# ACCUMULATOR.net
KiCad netlist of a schematic drawn in EAGLE
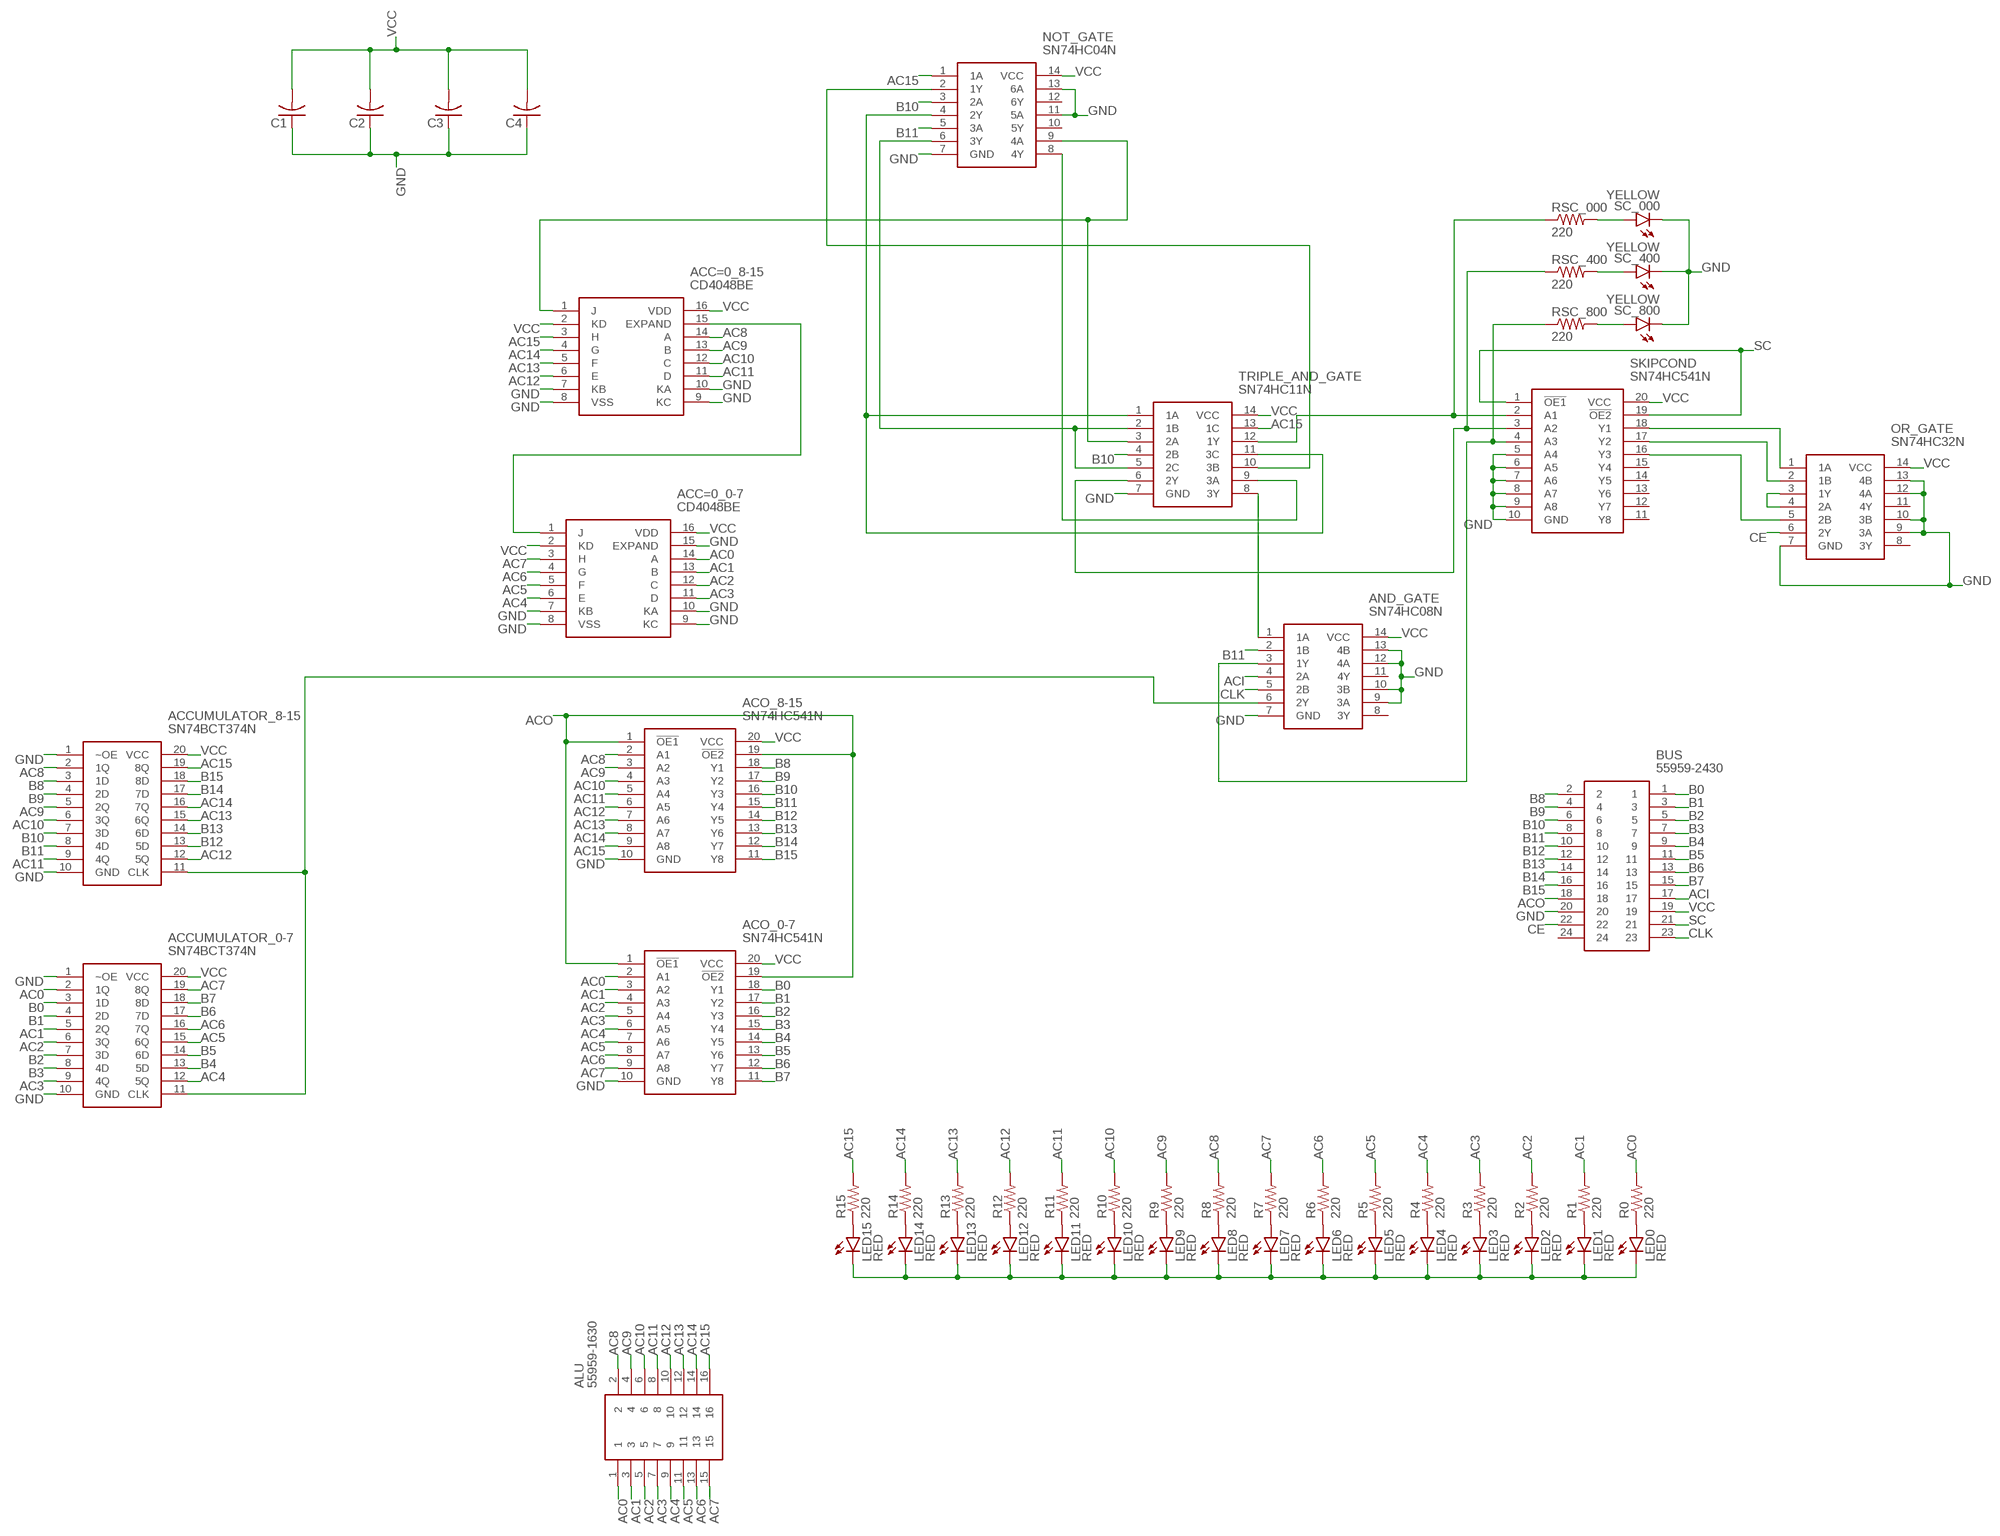
[diagram p0: schematic, sheet 1]

(export (version "E")
  (design (tool "Eeschema 10.0.6"))
  (components
    (comp (ref "ACC=0_0-7")
      (value "CD4048BE")
      (footprint "eagle-import:DIP254P762X508-16")
      (fields (field (name "MOUSER_PART_NUMBER") "595-CD4048BE"))
      (libsource (lib "eagle-import") (part "CD4048BE"))
    )
    (comp (ref "ACC=0_8-15")
      (value "CD4048BE")
      (footprint "eagle-import:DIP254P762X508-16")
      (fields (field (name "MOUSER_PART_NUMBER") "595-CD4048BE"))
      (libsource (lib "eagle-import") (part "CD4048BE"))
    )
    (comp (ref "ACCUMULATOR_0-7")
      (value "SN74BCT374N")
      (footprint "eagle-import:DIP254P762X508-20")
      (fields (field (name "MOUSER_PART_NUMBER") "595-SN74BCT374N"))
      (libsource (lib "eagle-import") (part "SN74BCT374N"))
    )
    (comp (ref "ACCUMULATOR_8-15")
      (value "SN74BCT374N")
      (footprint "eagle-import:DIP254P762X508-20")
      (fields (field (name "MOUSER_PART_NUMBER") "595-SN74BCT374N"))
      (libsource (lib "eagle-import") (part "SN74BCT374N"))
    )
    (comp (ref "ACO_0-7")
      (value "SN74HC541N")
      (footprint "eagle-import:DIP794W53P254L2540H508Q20N")
      (fields (field (name "MOUSER_PART_NUMBER") "595-SN74HC541N"))
      (libsource (lib "eagle-import") (part "SN74HC541N"))
    )
    (comp (ref "ACO_8-15")
      (value "SN74HC541N")
      (footprint "eagle-import:DIP794W53P254L2540H508Q20N")
      (fields (field (name "MOUSER_PART_NUMBER") "595-SN74HC541N"))
      (libsource (lib "eagle-import") (part "SN74HC541N"))
    )
    (comp (ref "ALU")
      (value "55959-1630")
      (footprint "eagle-import:SHDR16W65P250X200_2X8_1940X140")
      (fields (field (name "MOUSER_PART_NUMBER") "538-55959-1630"))
      (libsource (lib "eagle-import") (part "55959-1630"))
    )
    (comp (ref "AND_GATE")
      (value "SN74HC08N")
      (footprint "eagle-import:DIP794W53P254L1930H508Q14N")
      (fields (field (name "MOUSER_PART_NUMBER") "595-SN74HC08N"))
      (libsource (lib "eagle-import") (part "SN74HC08N"))
    )
    (comp (ref "BUS")
      (value "55959-2430")
      (footprint "eagle-import:559592430")
      (fields (field (name "MOUSER_PART_NUMBER") "538-55959-2430"))
      (libsource (lib "eagle-import") (part "55959-2430"))
    )
    (comp (ref "C1")
      (value "C-US025-024X044")
      (footprint "eagle-import:C025-024X044")
      (libsource (lib "eagle-import") (part "C-US025-024X044"))
    )
    (comp (ref "C2")
      (value "C-US025-024X044")
      (footprint "eagle-import:C025-024X044")
      (libsource (lib "eagle-import") (part "C-US025-024X044"))
    )
    (comp (ref "C3")
      (value "C-US025-024X044")
      (footprint "eagle-import:C025-024X044")
      (libsource (lib "eagle-import") (part "C-US025-024X044"))
    )
    (comp (ref "C4")
      (value "C-US025-024X044")
      (footprint "eagle-import:C025-024X044")
      (libsource (lib "eagle-import") (part "C-US025-024X044"))
    )
    (comp (ref "LED0")
      (value "RED")
      (footprint "eagle-import:LED3MM")
      (libsource (lib "eagle-import") (part "LED3MM"))
    )
    (comp (ref "LED1")
      (value "RED")
      (footprint "eagle-import:LED3MM")
      (libsource (lib "eagle-import") (part "LED3MM"))
    )
    (comp (ref "LED2")
      (value "RED")
      (footprint "eagle-import:LED3MM")
      (libsource (lib "eagle-import") (part "LED3MM"))
    )
    (comp (ref "LED3")
      (value "RED")
      (footprint "eagle-import:LED3MM")
      (libsource (lib "eagle-import") (part "LED3MM"))
    )
    (comp (ref "LED4")
      (value "RED")
      (footprint "eagle-import:LED3MM")
      (libsource (lib "eagle-import") (part "LED3MM"))
    )
    (comp (ref "LED5")
      (value "RED")
      (footprint "eagle-import:LED3MM")
      (libsource (lib "eagle-import") (part "LED3MM"))
    )
    (comp (ref "LED6")
      (value "RED")
      (footprint "eagle-import:LED3MM")
      (libsource (lib "eagle-import") (part "LED3MM"))
    )
    (comp (ref "LED7")
      (value "RED")
      (footprint "eagle-import:LED3MM")
      (libsource (lib "eagle-import") (part "LED3MM"))
    )
    (comp (ref "LED8")
      (value "RED")
      (footprint "eagle-import:LED3MM")
      (libsource (lib "eagle-import") (part "LED3MM"))
    )
    (comp (ref "LED9")
      (value "RED")
      (footprint "eagle-import:LED3MM")
      (libsource (lib "eagle-import") (part "LED3MM"))
    )
    (comp (ref "LED10")
      (value "RED")
      (footprint "eagle-import:LED3MM")
      (libsource (lib "eagle-import") (part "LED3MM"))
    )
    (comp (ref "LED11")
      (value "RED")
      (footprint "eagle-import:LED3MM")
      (libsource (lib "eagle-import") (part "LED3MM"))
    )
    (comp (ref "LED12")
      (value "RED")
      (footprint "eagle-import:LED3MM")
      (libsource (lib "eagle-import") (part "LED3MM"))
    )
    (comp (ref "LED13")
      (value "RED")
      (footprint "eagle-import:LED3MM")
      (libsource (lib "eagle-import") (part "LED3MM"))
    )
    (comp (ref "LED14")
      (value "RED")
      (footprint "eagle-import:LED3MM")
      (libsource (lib "eagle-import") (part "LED3MM"))
    )
    (comp (ref "LED15")
      (value "RED")
      (footprint "eagle-import:LED3MM")
      (libsource (lib "eagle-import") (part "LED3MM"))
    )
    (comp (ref "NOT_GATE")
      (value "SN74HC04N")
      (footprint "eagle-import:DIP794W53P254L1930H508Q14N")
      (fields (field (name "MOUSER_PART_NUMBER") "595-SN74HC04N"))
      (libsource (lib "eagle-import") (part "SN74HC04N"))
    )
    (comp (ref "OR_GATE")
      (value "SN74HC32N")
      (footprint "eagle-import:DIP794W53P254L1930H508Q14N")
      (fields (field (name "MOUSER_PART_NUMBER") "595-SN74HC32N"))
      (libsource (lib "eagle-import") (part "SN74HC32N"))
    )
    (comp (ref "R0")
      (value "220")
      (footprint "eagle-import:0204_7")
      (libsource (lib "eagle-import") (part "R-US_0204/7"))
    )
    (comp (ref "R1")
      (value "220")
      (footprint "eagle-import:0204_7")
      (libsource (lib "eagle-import") (part "R-US_0204/7"))
    )
    (comp (ref "R2")
      (value "220")
      (footprint "eagle-import:0204_7")
      (libsource (lib "eagle-import") (part "R-US_0204/7"))
    )
    (comp (ref "R3")
      (value "220")
      (footprint "eagle-import:0204_7")
      (libsource (lib "eagle-import") (part "R-US_0204/7"))
    )
    (comp (ref "R4")
      (value "220")
      (footprint "eagle-import:0204_7")
      (libsource (lib "eagle-import") (part "R-US_0204/7"))
    )
    (comp (ref "R5")
      (value "220")
      (footprint "eagle-import:0204_7")
      (libsource (lib "eagle-import") (part "R-US_0204/7"))
    )
    (comp (ref "R6")
      (value "220")
      (footprint "eagle-import:0204_7")
      (libsource (lib "eagle-import") (part "R-US_0204/7"))
    )
    (comp (ref "R7")
      (value "220")
      (footprint "eagle-import:0204_7")
      (libsource (lib "eagle-import") (part "R-US_0204/7"))
    )
    (comp (ref "R8")
      (value "220")
      (footprint "eagle-import:0204_7")
      (libsource (lib "eagle-import") (part "R-US_0204/7"))
    )
    (comp (ref "R9")
      (value "220")
      (footprint "eagle-import:0204_7")
      (libsource (lib "eagle-import") (part "R-US_0204/7"))
    )
    (comp (ref "R10")
      (value "220")
      (footprint "eagle-import:0204_7")
      (libsource (lib "eagle-import") (part "R-US_0204/7"))
    )
    (comp (ref "R11")
      (value "220")
      (footprint "eagle-import:0204_7")
      (libsource (lib "eagle-import") (part "R-US_0204/7"))
    )
    (comp (ref "R12")
      (value "220")
      (footprint "eagle-import:0204_7")
      (libsource (lib "eagle-import") (part "R-US_0204/7"))
    )
    (comp (ref "R13")
      (value "220")
      (footprint "eagle-import:0204_7")
      (libsource (lib "eagle-import") (part "R-US_0204/7"))
    )
    (comp (ref "R14")
      (value "220")
      (footprint "eagle-import:0204_7")
      (libsource (lib "eagle-import") (part "R-US_0204/7"))
    )
    (comp (ref "R15")
      (value "220")
      (footprint "eagle-import:0204_7")
      (libsource (lib "eagle-import") (part "R-US_0204/7"))
    )
    (comp (ref "RSC_000")
      (value "220")
      (footprint "eagle-import:0204_7")
      (libsource (lib "eagle-import") (part "R-US_0204/7"))
    )
    (comp (ref "RSC_400")
      (value "220")
      (footprint "eagle-import:0204_7")
      (libsource (lib "eagle-import") (part "R-US_0204/7"))
    )
    (comp (ref "RSC_800")
      (value "220")
      (footprint "eagle-import:0204_7")
      (libsource (lib "eagle-import") (part "R-US_0204/7"))
    )
    (comp (ref "SC_000")
      (value "YELLOW")
      (footprint "eagle-import:LED3MM")
      (libsource (lib "eagle-import") (part "LED3MM"))
    )
    (comp (ref "SC_400")
      (value "YELLOW")
      (footprint "eagle-import:LED3MM")
      (libsource (lib "eagle-import") (part "LED3MM"))
    )
    (comp (ref "SC_800")
      (value "YELLOW")
      (footprint "eagle-import:LED3MM")
      (libsource (lib "eagle-import") (part "LED3MM"))
    )
    (comp (ref "SKIPCOND")
      (value "SN74HC541N")
      (footprint "eagle-import:DIP794W53P254L2540H508Q20N")
      (fields (field (name "MOUSER_PART_NUMBER") "595-SN74HC541N"))
      (libsource (lib "eagle-import") (part "SN74HC541N"))
    )
    (comp (ref "TRIPLE_AND_GATE")
      (value "SN74HC11N")
      (footprint "eagle-import:DIP794W53P254L1930H508Q14N")
      (fields (field (name "MOUSER_PART_NUMBER") "595-SN74HC11N"))
      (libsource (lib "eagle-import") (part "SN74HC11N"))
    )
  )
  (nets
    (net (code "1") (name "/AC0") (class "Default")
      (node (ref "ACC=0_0-7") (pin "14") (pinfunction "A_14") (pintype "bidirectional"))
      (node (ref "ACCUMULATOR_0-7") (pin "2") (pinfunction "1Q_2") (pintype "bidirectional"))
      (node (ref "ACO_0-7") (pin "2") (pinfunction "A1_2") (pintype "bidirectional"))
      (node (ref "ALU") (pin "1") (pinfunction "1_1") (pintype "bidirectional"))
      (node (ref "R0") (pin "2") (pinfunction "2_2") (pintype "passive"))
    )
    (net (code "2") (name "/AC1") (class "Default")
      (node (ref "ACC=0_0-7") (pin "13") (pinfunction "B_13") (pintype "bidirectional"))
      (node (ref "ACCUMULATOR_0-7") (pin "5") (pinfunction "2Q_5") (pintype "bidirectional"))
      (node (ref "ACO_0-7") (pin "3") (pinfunction "A2_3") (pintype "bidirectional"))
      (node (ref "ALU") (pin "3") (pinfunction "3_3") (pintype "bidirectional"))
      (node (ref "R1") (pin "2") (pinfunction "2_2") (pintype "passive"))
    )
    (net (code "3") (name "/AC2") (class "Default")
      (node (ref "ACC=0_0-7") (pin "12") (pinfunction "C_12") (pintype "bidirectional"))
      (node (ref "ACCUMULATOR_0-7") (pin "6") (pinfunction "3Q_6") (pintype "bidirectional"))
      (node (ref "ACO_0-7") (pin "4") (pinfunction "A3_4") (pintype "bidirectional"))
      (node (ref "ALU") (pin "5") (pinfunction "5_5") (pintype "bidirectional"))
      (node (ref "R2") (pin "2") (pinfunction "2_2") (pintype "passive"))
    )
    (net (code "4") (name "/AC3") (class "Default")
      (node (ref "ACC=0_0-7") (pin "11") (pinfunction "D_11") (pintype "bidirectional"))
      (node (ref "ACCUMULATOR_0-7") (pin "9") (pinfunction "4Q_9") (pintype "bidirectional"))
      (node (ref "ACO_0-7") (pin "5") (pinfunction "A4_5") (pintype "bidirectional"))
      (node (ref "ALU") (pin "7") (pinfunction "7_7") (pintype "bidirectional"))
      (node (ref "R3") (pin "2") (pinfunction "2_2") (pintype "passive"))
    )
    (net (code "5") (name "/AC4") (class "Default")
      (node (ref "ACC=0_0-7") (pin "6") (pinfunction "E_6") (pintype "bidirectional"))
      (node (ref "ACCUMULATOR_0-7") (pin "12") (pinfunction "5Q_12") (pintype "bidirectional"))
      (node (ref "ACO_0-7") (pin "6") (pinfunction "A5_6") (pintype "bidirectional"))
      (node (ref "ALU") (pin "9") (pinfunction "9_9") (pintype "bidirectional"))
      (node (ref "R4") (pin "2") (pinfunction "2_2") (pintype "passive"))
    )
    (net (code "6") (name "/AC5") (class "Default")
      (node (ref "ACC=0_0-7") (pin "5") (pinfunction "F_5") (pintype "bidirectional"))
      (node (ref "ACCUMULATOR_0-7") (pin "15") (pinfunction "6Q_15") (pintype "bidirectional"))
      (node (ref "ACO_0-7") (pin "7") (pinfunction "A6_7") (pintype "bidirectional"))
      (node (ref "ALU") (pin "11") (pinfunction "11_11") (pintype "bidirectional"))
      (node (ref "R5") (pin "2") (pinfunction "2_2") (pintype "passive"))
    )
    (net (code "7") (name "/AC6") (class "Default")
      (node (ref "ACC=0_0-7") (pin "4") (pinfunction "G_4") (pintype "bidirectional"))
      (node (ref "ACCUMULATOR_0-7") (pin "16") (pinfunction "7Q_16") (pintype "bidirectional"))
      (node (ref "ACO_0-7") (pin "8") (pinfunction "A7_8") (pintype "bidirectional"))
      (node (ref "ALU") (pin "13") (pinfunction "13_13") (pintype "bidirectional"))
      (node (ref "R6") (pin "2") (pinfunction "2_2") (pintype "passive"))
    )
    (net (code "8") (name "/AC7") (class "Default")
      (node (ref "ACC=0_0-7") (pin "3") (pinfunction "H_3") (pintype "bidirectional"))
      (node (ref "ACCUMULATOR_0-7") (pin "19") (pinfunction "8Q_19") (pintype "bidirectional"))
      (node (ref "ACO_0-7") (pin "9") (pinfunction "A8_9") (pintype "bidirectional"))
      (node (ref "ALU") (pin "15") (pinfunction "15_15") (pintype "bidirectional"))
      (node (ref "R7") (pin "2") (pinfunction "2_2") (pintype "passive"))
    )
    (net (code "9") (name "/AC8") (class "Default")
      (node (ref "ACC=0_8-15") (pin "14") (pinfunction "A_14") (pintype "bidirectional"))
      (node (ref "ACCUMULATOR_8-15") (pin "2") (pinfunction "1Q_2") (pintype "bidirectional"))
      (node (ref "ACO_8-15") (pin "2") (pinfunction "A1_2") (pintype "bidirectional"))
      (node (ref "ALU") (pin "2") (pinfunction "2_2") (pintype "bidirectional"))
      (node (ref "R8") (pin "2") (pinfunction "2_2") (pintype "passive"))
    )
    (net (code "10") (name "/AC9") (class "Default")
      (node (ref "ACC=0_8-15") (pin "13") (pinfunction "B_13") (pintype "bidirectional"))
      (node (ref "ACCUMULATOR_8-15") (pin "5") (pinfunction "2Q_5") (pintype "bidirectional"))
      (node (ref "ACO_8-15") (pin "3") (pinfunction "A2_3") (pintype "bidirectional"))
      (node (ref "ALU") (pin "4") (pinfunction "4_4") (pintype "bidirectional"))
      (node (ref "R9") (pin "2") (pinfunction "2_2") (pintype "passive"))
    )
    (net (code "11") (name "/AC10") (class "Default")
      (node (ref "ACC=0_8-15") (pin "12") (pinfunction "C_12") (pintype "bidirectional"))
      (node (ref "ACCUMULATOR_8-15") (pin "6") (pinfunction "3Q_6") (pintype "bidirectional"))
      (node (ref "ACO_8-15") (pin "4") (pinfunction "A3_4") (pintype "bidirectional"))
      (node (ref "ALU") (pin "6") (pinfunction "6_6") (pintype "bidirectional"))
      (node (ref "R10") (pin "2") (pinfunction "2_2") (pintype "passive"))
    )
    (net (code "12") (name "/AC11") (class "Default")
      (node (ref "ACC=0_8-15") (pin "11") (pinfunction "D_11") (pintype "bidirectional"))
      (node (ref "ACCUMULATOR_8-15") (pin "9") (pinfunction "4Q_9") (pintype "bidirectional"))
      (node (ref "ACO_8-15") (pin "5") (pinfunction "A4_5") (pintype "bidirectional"))
      (node (ref "ALU") (pin "8") (pinfunction "8_8") (pintype "bidirectional"))
      (node (ref "R11") (pin "2") (pinfunction "2_2") (pintype "passive"))
    )
    (net (code "13") (name "/AC12") (class "Default")
      (node (ref "ACC=0_8-15") (pin "6") (pinfunction "E_6") (pintype "bidirectional"))
      (node (ref "ACCUMULATOR_8-15") (pin "12") (pinfunction "5Q_12") (pintype "bidirectional"))
      (node (ref "ACO_8-15") (pin "6") (pinfunction "A5_6") (pintype "bidirectional"))
      (node (ref "ALU") (pin "10") (pinfunction "10_10") (pintype "bidirectional"))
      (node (ref "R12") (pin "2") (pinfunction "2_2") (pintype "passive"))
    )
    (net (code "14") (name "/AC13") (class "Default")
      (node (ref "ACC=0_8-15") (pin "5") (pinfunction "F_5") (pintype "bidirectional"))
      (node (ref "ACCUMULATOR_8-15") (pin "15") (pinfunction "6Q_15") (pintype "bidirectional"))
      (node (ref "ACO_8-15") (pin "7") (pinfunction "A6_7") (pintype "bidirectional"))
      (node (ref "ALU") (pin "12") (pinfunction "12_12") (pintype "bidirectional"))
      (node (ref "R13") (pin "2") (pinfunction "2_2") (pintype "passive"))
    )
    (net (code "15") (name "/AC14") (class "Default")
      (node (ref "ACC=0_8-15") (pin "4") (pinfunction "G_4") (pintype "bidirectional"))
      (node (ref "ACCUMULATOR_8-15") (pin "16") (pinfunction "7Q_16") (pintype "bidirectional"))
      (node (ref "ACO_8-15") (pin "8") (pinfunction "A7_8") (pintype "bidirectional"))
      (node (ref "ALU") (pin "14") (pinfunction "14_14") (pintype "bidirectional"))
      (node (ref "R14") (pin "2") (pinfunction "2_2") (pintype "passive"))
    )
    (net (code "16") (name "/AC15") (class "Default")
      (node (ref "ACC=0_8-15") (pin "3") (pinfunction "H_3") (pintype "bidirectional"))
      (node (ref "ACCUMULATOR_8-15") (pin "19") (pinfunction "8Q_19") (pintype "bidirectional"))
      (node (ref "ACO_8-15") (pin "9") (pinfunction "A8_9") (pintype "bidirectional"))
      (node (ref "ALU") (pin "16") (pinfunction "16_16") (pintype "bidirectional"))
      (node (ref "NOT_GATE") (pin "1") (pinfunction "1A_1") (pintype "bidirectional"))
      (node (ref "R15") (pin "2") (pinfunction "2_2") (pintype "passive"))
      (node (ref "TRIPLE_AND_GATE") (pin "13") (pinfunction "1C_13") (pintype "bidirectional"))
    )
    (net (code "17") (name "/ACI") (class "Default")
      (node (ref "AND_GATE") (pin "4") (pinfunction "2A_4") (pintype "bidirectional"))
      (node (ref "BUS") (pin "17") (pinfunction "17_17") (pintype "bidirectional"))
    )
    (net (code "18") (name "/ACO") (class "Default")
      (node (ref "ACO_0-7") (pin "1") (pinfunction "~{OE1}_1") (pintype "bidirectional"))
      (node (ref "ACO_0-7") (pin "19") (pinfunction "~{OE2}_19") (pintype "bidirectional"))
      (node (ref "ACO_8-15") (pin "1") (pinfunction "~{OE1}_1") (pintype "bidirectional"))
      (node (ref "ACO_8-15") (pin "19") (pinfunction "~{OE2}_19") (pintype "bidirectional"))
      (node (ref "BUS") (pin "18") (pinfunction "18_18") (pintype "bidirectional"))
    )
    (net (code "19") (name "/B0") (class "Default")
      (node (ref "ACCUMULATOR_0-7") (pin "3") (pinfunction "1D_3") (pintype "bidirectional"))
      (node (ref "ACO_0-7") (pin "18") (pinfunction "Y1_18") (pintype "bidirectional"))
      (node (ref "BUS") (pin "1") (pinfunction "1_1") (pintype "bidirectional"))
    )
    (net (code "20") (name "/B1") (class "Default")
      (node (ref "ACCUMULATOR_0-7") (pin "4") (pinfunction "2D_4") (pintype "bidirectional"))
      (node (ref "ACO_0-7") (pin "17") (pinfunction "Y2_17") (pintype "bidirectional"))
      (node (ref "BUS") (pin "3") (pinfunction "3_3") (pintype "bidirectional"))
    )
    (net (code "21") (name "/B2") (class "Default")
      (node (ref "ACCUMULATOR_0-7") (pin "7") (pinfunction "3D_7") (pintype "bidirectional"))
      (node (ref "ACO_0-7") (pin "16") (pinfunction "Y3_16") (pintype "bidirectional"))
      (node (ref "BUS") (pin "5") (pinfunction "5_5") (pintype "bidirectional"))
    )
    (net (code "22") (name "/B3") (class "Default")
      (node (ref "ACCUMULATOR_0-7") (pin "8") (pinfunction "4D_8") (pintype "bidirectional"))
      (node (ref "ACO_0-7") (pin "15") (pinfunction "Y4_15") (pintype "bidirectional"))
      (node (ref "BUS") (pin "7") (pinfunction "7_7") (pintype "bidirectional"))
    )
    (net (code "23") (name "/B4") (class "Default")
      (node (ref "ACCUMULATOR_0-7") (pin "13") (pinfunction "5D_13") (pintype "bidirectional"))
      (node (ref "ACO_0-7") (pin "14") (pinfunction "Y5_14") (pintype "bidirectional"))
      (node (ref "BUS") (pin "9") (pinfunction "9_9") (pintype "bidirectional"))
    )
    (net (code "24") (name "/B5") (class "Default")
      (node (ref "ACCUMULATOR_0-7") (pin "14") (pinfunction "6D_14") (pintype "bidirectional"))
      (node (ref "ACO_0-7") (pin "13") (pinfunction "Y6_13") (pintype "bidirectional"))
      (node (ref "BUS") (pin "11") (pinfunction "11_11") (pintype "bidirectional"))
    )
    (net (code "25") (name "/B6") (class "Default")
      (node (ref "ACCUMULATOR_0-7") (pin "17") (pinfunction "7D_17") (pintype "bidirectional"))
      (node (ref "ACO_0-7") (pin "12") (pinfunction "Y7_12") (pintype "bidirectional"))
      (node (ref "BUS") (pin "13") (pinfunction "13_13") (pintype "bidirectional"))
    )
    (net (code "26") (name "/B7") (class "Default")
      (node (ref "ACCUMULATOR_0-7") (pin "18") (pinfunction "8D_18") (pintype "bidirectional"))
      (node (ref "ACO_0-7") (pin "11") (pinfunction "Y8_11") (pintype "bidirectional"))
      (node (ref "BUS") (pin "15") (pinfunction "15_15") (pintype "bidirectional"))
    )
    (net (code "27") (name "/B8") (class "Default")
      (node (ref "ACCUMULATOR_8-15") (pin "3") (pinfunction "1D_3") (pintype "bidirectional"))
      (node (ref "ACO_8-15") (pin "18") (pinfunction "Y1_18") (pintype "bidirectional"))
      (node (ref "BUS") (pin "2") (pinfunction "2_2") (pintype "bidirectional"))
    )
    (net (code "28") (name "/B9") (class "Default")
      (node (ref "ACCUMULATOR_8-15") (pin "4") (pinfunction "2D_4") (pintype "bidirectional"))
      (node (ref "ACO_8-15") (pin "17") (pinfunction "Y2_17") (pintype "bidirectional"))
      (node (ref "BUS") (pin "4") (pinfunction "4_4") (pintype "bidirectional"))
    )
    (net (code "29") (name "/B10") (class "Default")
      (node (ref "ACCUMULATOR_8-15") (pin "7") (pinfunction "3D_7") (pintype "bidirectional"))
      (node (ref "ACO_8-15") (pin "16") (pinfunction "Y3_16") (pintype "bidirectional"))
      (node (ref "BUS") (pin "6") (pinfunction "6_6") (pintype "bidirectional"))
      (node (ref "NOT_GATE") (pin "3") (pinfunction "2A_3") (pintype "bidirectional"))
      (node (ref "TRIPLE_AND_GATE") (pin "4") (pinfunction "2B_4") (pintype "bidirectional"))
    )
    (net (code "30") (name "/B11") (class "Default")
      (node (ref "ACCUMULATOR_8-15") (pin "8") (pinfunction "4D_8") (pintype "bidirectional"))
      (node (ref "ACO_8-15") (pin "15") (pinfunction "Y4_15") (pintype "bidirectional"))
      (node (ref "AND_GATE") (pin "2") (pinfunction "1B_2") (pintype "bidirectional"))
      (node (ref "BUS") (pin "8") (pinfunction "8_8") (pintype "bidirectional"))
      (node (ref "NOT_GATE") (pin "5") (pinfunction "3A_5") (pintype "bidirectional"))
    )
    (net (code "31") (name "/B12") (class "Default")
      (node (ref "ACCUMULATOR_8-15") (pin "13") (pinfunction "5D_13") (pintype "bidirectional"))
      (node (ref "ACO_8-15") (pin "14") (pinfunction "Y5_14") (pintype "bidirectional"))
      (node (ref "BUS") (pin "10") (pinfunction "10_10") (pintype "bidirectional"))
    )
    (net (code "32") (name "/B13") (class "Default")
      (node (ref "ACCUMULATOR_8-15") (pin "14") (pinfunction "6D_14") (pintype "bidirectional"))
      (node (ref "ACO_8-15") (pin "13") (pinfunction "Y6_13") (pintype "bidirectional"))
      (node (ref "BUS") (pin "12") (pinfunction "12_12") (pintype "bidirectional"))
    )
    (net (code "33") (name "/B14") (class "Default")
      (node (ref "ACCUMULATOR_8-15") (pin "17") (pinfunction "7D_17") (pintype "bidirectional"))
      (node (ref "ACO_8-15") (pin "12") (pinfunction "Y7_12") (pintype "bidirectional"))
      (node (ref "BUS") (pin "14") (pinfunction "14_14") (pintype "bidirectional"))
    )
    (net (code "34") (name "/B15") (class "Default")
      (node (ref "ACCUMULATOR_8-15") (pin "18") (pinfunction "8D_18") (pintype "bidirectional"))
      (node (ref "ACO_8-15") (pin "11") (pinfunction "Y8_11") (pintype "bidirectional"))
      (node (ref "BUS") (pin "16") (pinfunction "16_16") (pintype "bidirectional"))
    )
    (net (code "35") (name "/CE") (class "Default")
      (node (ref "BUS") (pin "22") (pinfunction "22_22") (pintype "bidirectional"))
      (node (ref "OR_GATE") (pin "6") (pinfunction "2Y_6") (pintype "bidirectional"))
    )
    (net (code "36") (name "/CLK") (class "Default")
      (node (ref "AND_GATE") (pin "5") (pinfunction "2B_5") (pintype "bidirectional"))
      (node (ref "BUS") (pin "23") (pinfunction "23_23") (pintype "bidirectional"))
    )
    (net (code "37") (name "/GND") (class "Default")
      (node (ref "ACC=0_0-7") (pin "10") (pinfunction "KA_10") (pintype "bidirectional"))
      (node (ref "ACC=0_0-7") (pin "15") (pinfunction "EXPAND_15") (pintype "bidirectional"))
      (node (ref "ACC=0_0-7") (pin "7") (pinfunction "KB_7") (pintype "bidirectional"))
      (node (ref "ACC=0_0-7") (pin "8") (pinfunction "VSS_8") (pintype "bidirectional"))
      (node (ref "ACC=0_0-7") (pin "9") (pinfunction "KC_9") (pintype "bidirectional"))
      (node (ref "ACC=0_8-15") (pin "10") (pinfunction "KA_10") (pintype "bidirectional"))
      (node (ref "ACC=0_8-15") (pin "7") (pinfunction "KB_7") (pintype "bidirectional"))
      (node (ref "ACC=0_8-15") (pin "8") (pinfunction "VSS_8") (pintype "bidirectional"))
      (node (ref "ACC=0_8-15") (pin "9") (pinfunction "KC_9") (pintype "bidirectional"))
      (node (ref "ACCUMULATOR_0-7") (pin "1") (pinfunction "~{OE}_1") (pintype "bidirectional"))
      (node (ref "ACCUMULATOR_0-7") (pin "10") (pinfunction "GND_10") (pintype "bidirectional"))
      (node (ref "ACCUMULATOR_8-15") (pin "1") (pinfunction "~{OE}_1") (pintype "bidirectional"))
      (node (ref "ACCUMULATOR_8-15") (pin "10") (pinfunction "GND_10") (pintype "bidirectional"))
      (node (ref "ACO_0-7") (pin "10") (pinfunction "GND_10") (pintype "bidirectional"))
      (node (ref "ACO_8-15") (pin "10") (pinfunction "GND_10") (pintype "bidirectional"))
      (node (ref "AND_GATE") (pin "10") (pinfunction "3B_10") (pintype "bidirectional"))
      (node (ref "AND_GATE") (pin "12") (pinfunction "4A_12") (pintype "bidirectional"))
      (node (ref "AND_GATE") (pin "13") (pinfunction "4B_13") (pintype "bidirectional"))
      (node (ref "AND_GATE") (pin "7") (pinfunction "GND_7") (pintype "bidirectional"))
      (node (ref "AND_GATE") (pin "9") (pinfunction "3A_9") (pintype "bidirectional"))
      (node (ref "BUS") (pin "20") (pinfunction "20_20") (pintype "bidirectional"))
      (node (ref "C1") (pin "1") (pinfunction "1_1") (pintype "passive"))
      (node (ref "C2") (pin "1") (pinfunction "1_1") (pintype "passive"))
      (node (ref "C3") (pin "1") (pinfunction "1_1") (pintype "passive"))
      (node (ref "C4") (pin "1") (pinfunction "1_1") (pintype "passive"))
      (node (ref "NOT_GATE") (pin "11") (pinfunction "5A_11") (pintype "bidirectional"))
      (node (ref "NOT_GATE") (pin "13") (pinfunction "6A_13") (pintype "bidirectional"))
      (node (ref "NOT_GATE") (pin "7") (pinfunction "GND_7") (pintype "bidirectional"))
      (node (ref "OR_GATE") (pin "10") (pinfunction "3B_10") (pintype "bidirectional"))
      (node (ref "OR_GATE") (pin "12") (pinfunction "4A_12") (pintype "bidirectional"))
      (node (ref "OR_GATE") (pin "13") (pinfunction "4B_13") (pintype "bidirectional"))
      (node (ref "OR_GATE") (pin "7") (pinfunction "GND_7") (pintype "bidirectional"))
      (node (ref "OR_GATE") (pin "9") (pinfunction "3A_9") (pintype "bidirectional"))
      (node (ref "SC_000") (pin "K") (pinfunction "C_K") (pintype "passive"))
      (node (ref "SC_400") (pin "K") (pinfunction "C_K") (pintype "passive"))
      (node (ref "SC_800") (pin "K") (pinfunction "C_K") (pintype "passive"))
      (node (ref "SKIPCOND") (pin "10") (pinfunction "GND_10") (pintype "bidirectional"))
      (node (ref "SKIPCOND") (pin "5") (pinfunction "A4_5") (pintype "bidirectional"))
      (node (ref "SKIPCOND") (pin "6") (pinfunction "A5_6") (pintype "bidirectional"))
      (node (ref "SKIPCOND") (pin "7") (pinfunction "A6_7") (pintype "bidirectional"))
      (node (ref "SKIPCOND") (pin "8") (pinfunction "A7_8") (pintype "bidirectional"))
      (node (ref "SKIPCOND") (pin "9") (pinfunction "A8_9") (pintype "bidirectional"))
      (node (ref "TRIPLE_AND_GATE") (pin "7") (pinfunction "GND_7") (pintype "bidirectional"))
    )
    (net (code "38") (name "/SC") (class "Default")
      (node (ref "BUS") (pin "21") (pinfunction "21_21") (pintype "bidirectional"))
      (node (ref "SKIPCOND") (pin "1") (pinfunction "~{OE1}_1") (pintype "bidirectional"))
      (node (ref "SKIPCOND") (pin "19") (pinfunction "~{OE2}_19") (pintype "bidirectional"))
    )
    (net (code "39") (name "/VCC") (class "Default")
      (node (ref "ACC=0_0-7") (pin "16") (pinfunction "VDD_16") (pintype "bidirectional"))
      (node (ref "ACC=0_0-7") (pin "2") (pinfunction "KD_2") (pintype "bidirectional"))
      (node (ref "ACC=0_8-15") (pin "16") (pinfunction "VDD_16") (pintype "bidirectional"))
      (node (ref "ACC=0_8-15") (pin "2") (pinfunction "KD_2") (pintype "bidirectional"))
      (node (ref "ACCUMULATOR_0-7") (pin "20") (pinfunction "VCC_20") (pintype "bidirectional"))
      (node (ref "ACCUMULATOR_8-15") (pin "20") (pinfunction "VCC_20") (pintype "bidirectional"))
      (node (ref "ACO_0-7") (pin "20") (pinfunction "VCC_20") (pintype "bidirectional"))
      (node (ref "ACO_8-15") (pin "20") (pinfunction "VCC_20") (pintype "bidirectional"))
      (node (ref "AND_GATE") (pin "14") (pinfunction "VCC_14") (pintype "bidirectional"))
      (node (ref "BUS") (pin "19") (pinfunction "19_19") (pintype "bidirectional"))
      (node (ref "C1") (pin "2") (pinfunction "2_2") (pintype "passive"))
      (node (ref "C2") (pin "2") (pinfunction "2_2") (pintype "passive"))
      (node (ref "C3") (pin "2") (pinfunction "2_2") (pintype "passive"))
      (node (ref "C4") (pin "2") (pinfunction "2_2") (pintype "passive"))
      (node (ref "NOT_GATE") (pin "14") (pinfunction "VCC_14") (pintype "bidirectional"))
      (node (ref "OR_GATE") (pin "14") (pinfunction "VCC_14") (pintype "bidirectional"))
      (node (ref "SKIPCOND") (pin "20") (pinfunction "VCC_20") (pintype "bidirectional"))
      (node (ref "TRIPLE_AND_GATE") (pin "14") (pinfunction "VCC_14") (pintype "bidirectional"))
    )
    (net (code "40") (name "Net-(ACC=0_0-7-J)") (class "Default")
      (node (ref "ACC=0_0-7") (pin "1") (pinfunction "J_1") (pintype "bidirectional"))
      (node (ref "ACC=0_8-15") (pin "15") (pinfunction "EXPAND_15") (pintype "bidirectional"))
    )
    (net (code "41") (name "Net-(ACC=0_8-15-J)") (class "Default")
      (node (ref "ACC=0_8-15") (pin "1") (pinfunction "J_1") (pintype "bidirectional"))
      (node (ref "NOT_GATE") (pin "9") (pinfunction "4A_9") (pintype "bidirectional"))
      (node (ref "TRIPLE_AND_GATE") (pin "3") (pinfunction "2A_3") (pintype "bidirectional"))
    )
    (net (code "42") (name "Net-(ACCUMULATOR_0-7-CLK)") (class "Default")
      (node (ref "ACCUMULATOR_0-7") (pin "11") (pinfunction "CLK_11") (pintype "bidirectional"))
      (node (ref "ACCUMULATOR_8-15") (pin "11") (pinfunction "CLK_11") (pintype "bidirectional"))
      (node (ref "AND_GATE") (pin "6") (pinfunction "2Y_6") (pintype "bidirectional"))
    )
    (net (code "43") (name "Net-(AND_GATE-1A)") (class "Default")
      (node (ref "AND_GATE") (pin "1") (pinfunction "1A_1") (pintype "bidirectional"))
      (node (ref "TRIPLE_AND_GATE") (pin "8") (pinfunction "3Y_8") (pintype "bidirectional"))
    )
    (net (code "44") (name "Net-(AND_GATE-1Y)") (class "Default")
      (node (ref "AND_GATE") (pin "3") (pinfunction "1Y_3") (pintype "bidirectional"))
      (node (ref "RSC_800") (pin "1") (pinfunction "1_1") (pintype "passive"))
      (node (ref "SKIPCOND") (pin "4") (pinfunction "A3_4") (pintype "bidirectional"))
    )
    (net (code "45") (name "Net-(LED0-C)") (class "Default")
      (node (ref "LED0") (pin "K") (pinfunction "C_K") (pintype "passive"))
      (node (ref "LED1") (pin "K") (pinfunction "C_K") (pintype "passive"))
      (node (ref "LED10") (pin "K") (pinfunction "C_K") (pintype "passive"))
      (node (ref "LED11") (pin "K") (pinfunction "C_K") (pintype "passive"))
      (node (ref "LED12") (pin "K") (pinfunction "C_K") (pintype "passive"))
      (node (ref "LED13") (pin "K") (pinfunction "C_K") (pintype "passive"))
      (node (ref "LED14") (pin "K") (pinfunction "C_K") (pintype "passive"))
      (node (ref "LED15") (pin "K") (pinfunction "C_K") (pintype "passive"))
      (node (ref "LED2") (pin "K") (pinfunction "C_K") (pintype "passive"))
      (node (ref "LED3") (pin "K") (pinfunction "C_K") (pintype "passive"))
      (node (ref "LED4") (pin "K") (pinfunction "C_K") (pintype "passive"))
      (node (ref "LED5") (pin "K") (pinfunction "C_K") (pintype "passive"))
      (node (ref "LED6") (pin "K") (pinfunction "C_K") (pintype "passive"))
      (node (ref "LED7") (pin "K") (pinfunction "C_K") (pintype "passive"))
      (node (ref "LED8") (pin "K") (pinfunction "C_K") (pintype "passive"))
      (node (ref "LED9") (pin "K") (pinfunction "C_K") (pintype "passive"))
    )
    (net (code "46") (name "Net-(LED0-PadA)") (class "Default")
      (node (ref "LED0") (pin "A") (pinfunction "A_A") (pintype "passive"))
      (node (ref "R0") (pin "1") (pinfunction "1_1") (pintype "passive"))
    )
    (net (code "47") (name "Net-(LED1-PadA)") (class "Default")
      (node (ref "LED1") (pin "A") (pinfunction "A_A") (pintype "passive"))
      (node (ref "R1") (pin "1") (pinfunction "1_1") (pintype "passive"))
    )
    (net (code "48") (name "Net-(LED2-PadA)") (class "Default")
      (node (ref "LED2") (pin "A") (pinfunction "A_A") (pintype "passive"))
      (node (ref "R2") (pin "1") (pinfunction "1_1") (pintype "passive"))
    )
    (net (code "49") (name "Net-(LED3-PadA)") (class "Default")
      (node (ref "LED3") (pin "A") (pinfunction "A_A") (pintype "passive"))
      (node (ref "R3") (pin "1") (pinfunction "1_1") (pintype "passive"))
    )
    (net (code "50") (name "Net-(LED4-PadA)") (class "Default")
      (node (ref "LED4") (pin "A") (pinfunction "A_A") (pintype "passive"))
      (node (ref "R4") (pin "1") (pinfunction "1_1") (pintype "passive"))
    )
    (net (code "51") (name "Net-(LED5-PadA)") (class "Default")
      (node (ref "LED5") (pin "A") (pinfunction "A_A") (pintype "passive"))
      (node (ref "R5") (pin "1") (pinfunction "1_1") (pintype "passive"))
    )
    (net (code "52") (name "Net-(LED6-PadA)") (class "Default")
      (node (ref "LED6") (pin "A") (pinfunction "A_A") (pintype "passive"))
      (node (ref "R6") (pin "1") (pinfunction "1_1") (pintype "passive"))
    )
    (net (code "53") (name "Net-(LED7-PadA)") (class "Default")
      (node (ref "LED7") (pin "A") (pinfunction "A_A") (pintype "passive"))
      (node (ref "R7") (pin "1") (pinfunction "1_1") (pintype "passive"))
    )
    (net (code "54") (name "Net-(LED8-PadA)") (class "Default")
      (node (ref "LED8") (pin "A") (pinfunction "A_A") (pintype "passive"))
      (node (ref "R8") (pin "1") (pinfunction "1_1") (pintype "passive"))
    )
    (net (code "55") (name "Net-(LED9-PadA)") (class "Default")
      (node (ref "LED9") (pin "A") (pinfunction "A_A") (pintype "passive"))
      (node (ref "R9") (pin "1") (pinfunction "1_1") (pintype "passive"))
    )
    (net (code "56") (name "Net-(LED10-PadA)") (class "Default")
      (node (ref "LED10") (pin "A") (pinfunction "A_A") (pintype "passive"))
      (node (ref "R10") (pin "1") (pinfunction "1_1") (pintype "passive"))
    )
    (net (code "57") (name "Net-(LED11-PadA)") (class "Default")
      (node (ref "LED11") (pin "A") (pinfunction "A_A") (pintype "passive"))
      (node (ref "R11") (pin "1") (pinfunction "1_1") (pintype "passive"))
    )
    (net (code "58") (name "Net-(LED12-PadA)") (class "Default")
      (node (ref "LED12") (pin "A") (pinfunction "A_A") (pintype "passive"))
      (node (ref "R12") (pin "1") (pinfunction "1_1") (pintype "passive"))
    )
    (net (code "59") (name "Net-(LED13-PadA)") (class "Default")
      (node (ref "LED13") (pin "A") (pinfunction "A_A") (pintype "passive"))
      (node (ref "R13") (pin "1") (pinfunction "1_1") (pintype "passive"))
    )
    (net (code "60") (name "Net-(LED14-PadA)") (class "Default")
      (node (ref "LED14") (pin "A") (pinfunction "A_A") (pintype "passive"))
      (node (ref "R14") (pin "1") (pinfunction "1_1") (pintype "passive"))
    )
    (net (code "61") (name "Net-(LED15-PadA)") (class "Default")
      (node (ref "LED15") (pin "A") (pinfunction "A_A") (pintype "passive"))
      (node (ref "R15") (pin "1") (pinfunction "1_1") (pintype "passive"))
    )
    (net (code "62") (name "Net-(NOT_GATE-1Y)") (class "Default")
      (node (ref "NOT_GATE") (pin "2") (pinfunction "1Y_2") (pintype "bidirectional"))
      (node (ref "TRIPLE_AND_GATE") (pin "10") (pinfunction "3B_10") (pintype "bidirectional"))
    )
    (net (code "63") (name "Net-(NOT_GATE-2Y)") (class "Default")
      (node (ref "NOT_GATE") (pin "4") (pinfunction "2Y_4") (pintype "bidirectional"))
      (node (ref "TRIPLE_AND_GATE") (pin "1") (pinfunction "1A_1") (pintype "bidirectional"))
      (node (ref "TRIPLE_AND_GATE") (pin "11") (pinfunction "3C_11") (pintype "bidirectional"))
    )
    (net (code "64") (name "Net-(NOT_GATE-3Y)") (class "Default")
      (node (ref "NOT_GATE") (pin "6") (pinfunction "3Y_6") (pintype "bidirectional"))
      (node (ref "TRIPLE_AND_GATE") (pin "2") (pinfunction "1B_2") (pintype "bidirectional"))
      (node (ref "TRIPLE_AND_GATE") (pin "5") (pinfunction "2C_5") (pintype "bidirectional"))
    )
    (net (code "65") (name "Net-(NOT_GATE-4Y)") (class "Default")
      (node (ref "NOT_GATE") (pin "8") (pinfunction "4Y_8") (pintype "bidirectional"))
      (node (ref "TRIPLE_AND_GATE") (pin "9") (pinfunction "3A_9") (pintype "bidirectional"))
    )
    (net (code "66") (name "Net-(OR_GATE-1A)") (class "Default")
      (node (ref "OR_GATE") (pin "1") (pinfunction "1A_1") (pintype "bidirectional"))
      (node (ref "SKIPCOND") (pin "18") (pinfunction "Y1_18") (pintype "bidirectional"))
    )
    (net (code "67") (name "Net-(OR_GATE-1B)") (class "Default")
      (node (ref "OR_GATE") (pin "2") (pinfunction "1B_2") (pintype "bidirectional"))
      (node (ref "SKIPCOND") (pin "17") (pinfunction "Y2_17") (pintype "bidirectional"))
    )
    (net (code "68") (name "Net-(OR_GATE-1Y)") (class "Default")
      (node (ref "OR_GATE") (pin "3") (pinfunction "1Y_3") (pintype "bidirectional"))
      (node (ref "OR_GATE") (pin "4") (pinfunction "2A_4") (pintype "bidirectional"))
    )
    (net (code "69") (name "Net-(OR_GATE-2B)") (class "Default")
      (node (ref "OR_GATE") (pin "5") (pinfunction "2B_5") (pintype "bidirectional"))
      (node (ref "SKIPCOND") (pin "16") (pinfunction "Y3_16") (pintype "bidirectional"))
    )
    (net (code "70") (name "Net-(RSC_000-Pad2)") (class "Default")
      (node (ref "RSC_000") (pin "2") (pinfunction "2_2") (pintype "passive"))
      (node (ref "SC_000") (pin "A") (pinfunction "A_A") (pintype "passive"))
    )
    (net (code "71") (name "Net-(RSC_400-Pad2)") (class "Default")
      (node (ref "RSC_400") (pin "2") (pinfunction "2_2") (pintype "passive"))
      (node (ref "SC_400") (pin "A") (pinfunction "A_A") (pintype "passive"))
    )
    (net (code "72") (name "Net-(RSC_800-Pad2)") (class "Default")
      (node (ref "RSC_800") (pin "2") (pinfunction "2_2") (pintype "passive"))
      (node (ref "SC_800") (pin "A") (pinfunction "A_A") (pintype "passive"))
    )
    (net (code "73") (name "Net-(SKIPCOND-A1)") (class "Default")
      (node (ref "RSC_000") (pin "1") (pinfunction "1_1") (pintype "passive"))
      (node (ref "SKIPCOND") (pin "2") (pinfunction "A1_2") (pintype "bidirectional"))
      (node (ref "TRIPLE_AND_GATE") (pin "12") (pinfunction "1Y_12") (pintype "bidirectional"))
    )
    (net (code "74") (name "Net-(SKIPCOND-A2)") (class "Default")
      (node (ref "RSC_400") (pin "1") (pinfunction "1_1") (pintype "passive"))
      (node (ref "SKIPCOND") (pin "3") (pinfunction "A2_3") (pintype "bidirectional"))
      (node (ref "TRIPLE_AND_GATE") (pin "6") (pinfunction "2Y_6") (pintype "bidirectional"))
    )
    (net (code "75") (name "unconnected-(AND_GATE-3Y-Pad8)") (class "Default")
      (node (ref "AND_GATE") (pin "8") (pinfunction "3Y_8") (pintype "bidirectional"))
    )
    (net (code "76") (name "unconnected-(AND_GATE-4Y-Pad11)") (class "Default")
      (node (ref "AND_GATE") (pin "11") (pinfunction "4Y_11") (pintype "bidirectional"))
    )
    (net (code "77") (name "unconnected-(BUS-Pad24)") (class "Default")
      (node (ref "BUS") (pin "24") (pinfunction "24_24") (pintype "bidirectional"))
    )
    (net (code "78") (name "unconnected-(NOT_GATE-5Y-Pad10)") (class "Default")
      (node (ref "NOT_GATE") (pin "10") (pinfunction "5Y_10") (pintype "bidirectional"))
    )
    (net (code "79") (name "unconnected-(NOT_GATE-6Y-Pad12)") (class "Default")
      (node (ref "NOT_GATE") (pin "12") (pinfunction "6Y_12") (pintype "bidirectional"))
    )
    (net (code "80") (name "unconnected-(OR_GATE-3Y-Pad8)") (class "Default")
      (node (ref "OR_GATE") (pin "8") (pinfunction "3Y_8") (pintype "bidirectional"))
    )
    (net (code "81") (name "unconnected-(OR_GATE-4Y-Pad11)") (class "Default")
      (node (ref "OR_GATE") (pin "11") (pinfunction "4Y_11") (pintype "bidirectional"))
    )
    (net (code "82") (name "unconnected-(SKIPCOND-Y4-Pad15)") (class "Default")
      (node (ref "SKIPCOND") (pin "15") (pinfunction "Y4_15") (pintype "bidirectional"))
    )
    (net (code "83") (name "unconnected-(SKIPCOND-Y5-Pad14)") (class "Default")
      (node (ref "SKIPCOND") (pin "14") (pinfunction "Y5_14") (pintype "bidirectional"))
    )
    (net (code "84") (name "unconnected-(SKIPCOND-Y6-Pad13)") (class "Default")
      (node (ref "SKIPCOND") (pin "13") (pinfunction "Y6_13") (pintype "bidirectional"))
    )
    (net (code "85") (name "unconnected-(SKIPCOND-Y7-Pad12)") (class "Default")
      (node (ref "SKIPCOND") (pin "12") (pinfunction "Y7_12") (pintype "bidirectional"))
    )
    (net (code "86") (name "unconnected-(SKIPCOND-Y8-Pad11)") (class "Default")
      (node (ref "SKIPCOND") (pin "11") (pinfunction "Y8_11") (pintype "bidirectional"))
    )
  )
)
